# Excercise_000_Completed.net
KiCad netlist of a schematic drawn in EAGLE
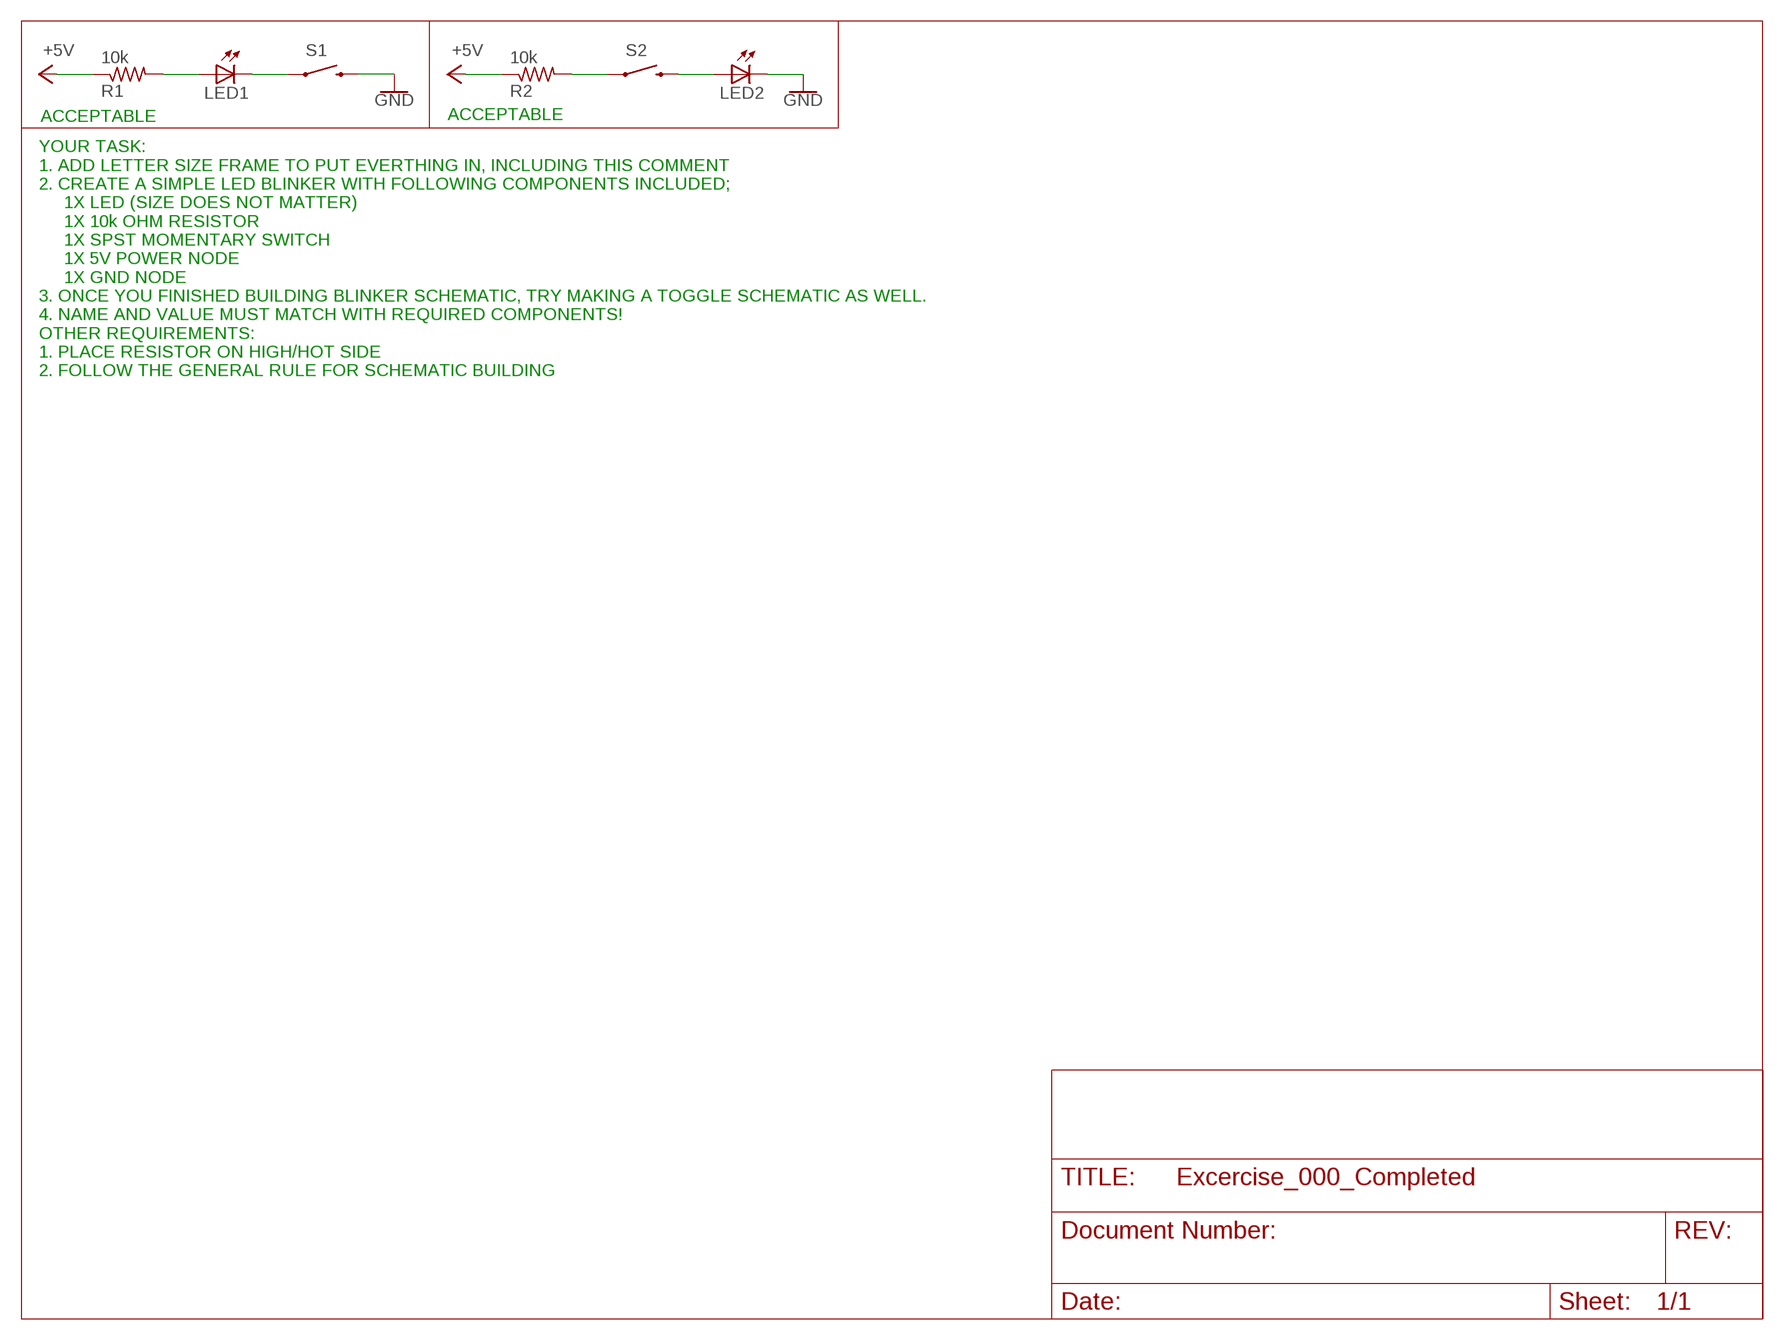
[diagram p0: schematic, sheet 1]

(export (version "E")
  (design (tool "Eeschema 10.0.6"))
  (components
    (comp (ref "LED1")
      (value "LED5MM")
      (footprint "eagle-import:LED5MM")
      (libsource (lib "eagle-import") (part "LED5MM"))
    )
    (comp (ref "LED2")
      (value "LED5MM")
      (footprint "eagle-import:LED5MM")
      (libsource (lib "eagle-import") (part "LED5MM"))
    )
    (comp (ref "R1")
      (value "10k")
      (footprint "eagle-import:R0805")
      (libsource (lib "eagle-import") (part "R-US_R0805"))
    )
    (comp (ref "R2")
      (value "10k")
      (footprint "eagle-import:R0805")
      (libsource (lib "eagle-import") (part "R-US_R0805"))
    )
    (comp (ref "S1")
      (value "SWITCH-MOMENTARY-SPSTSMD-3")
      (footprint "eagle-import:TACTILE_SWITCH_SMD-3")
      (libsource (lib "eagle-import") (part "SWITCH-MOMENTARY-SPSTSMD-3"))
    )
    (comp (ref "S2")
      (value "SWITCH-MOMENTARY-SPSTSMD-3")
      (footprint "eagle-import:TACTILE_SWITCH_SMD-3")
      (libsource (lib "eagle-import") (part "SWITCH-MOMENTARY-SPSTSMD-3"))
    )
  )
  (nets
    (net (code "1") (name "+5V") (class "Default")
      (node (ref "R1") (pin "1") (pinfunction "1_1") (pintype "passive"))
      (node (ref "R2") (pin "1") (pinfunction "1_1") (pintype "passive"))
    )
    (net (code "2") (name "GND") (class "Default")
      (node (ref "LED2") (pin "K") (pinfunction "C_K") (pintype "passive"))
      (node (ref "S1") (pin "4") (pinfunction "2_4") (pintype "passive"))
    )
    (net (code "3") (name "Net-(LED1-C)") (class "Default")
      (node (ref "LED1") (pin "K") (pinfunction "C_K") (pintype "passive"))
      (node (ref "S1") (pin "1") (pinfunction "1_1") (pintype "passive"))
    )
    (net (code "4") (name "Net-(LED1-PadA)") (class "Default")
      (node (ref "LED1") (pin "A") (pinfunction "A_A") (pintype "passive"))
      (node (ref "R1") (pin "2") (pinfunction "2_2") (pintype "passive"))
    )
    (net (code "5") (name "Net-(R2-Pad2)") (class "Default")
      (node (ref "R2") (pin "2") (pinfunction "2_2") (pintype "passive"))
      (node (ref "S2") (pin "1") (pinfunction "1_1") (pintype "passive"))
    )
    (net (code "6") (name "Net-(S2-2)") (class "Default")
      (node (ref "LED2") (pin "A") (pinfunction "A_A") (pintype "passive"))
      (node (ref "S2") (pin "4") (pinfunction "2_4") (pintype "passive"))
    )
  )
)
